# Dev.net
KiCad netlist of a schematic drawn in Altium Designer
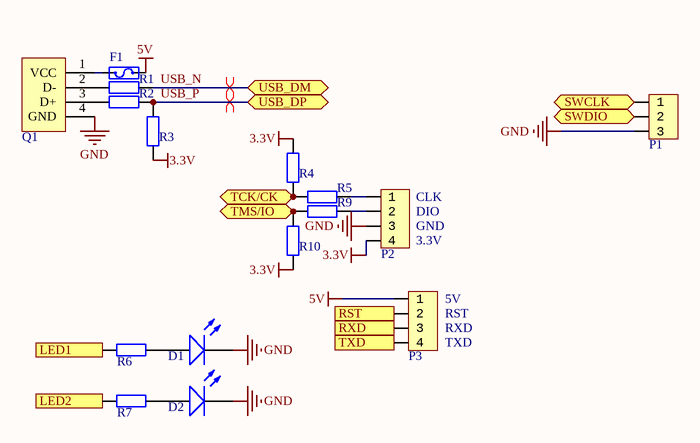
[diagram p0: Dev.SchDoc]

(export (version "E")
  (design (tool "Eeschema 10.0.6"))
  (components
    (comp (ref "D1")
      (value "RED")
      (footprint "LED-0603")
      (description "发光二极管")
      (libsource (lib "Power_Lib_Altium") (part "LED"))
    )
    (comp (ref "D2")
      (value "GREEN")
      (footprint "LED-0603")
      (description "发光二极管")
      (libsource (lib "Power_Lib_Altium") (part "LED"))
    )
    (comp (ref "F1")
      (value "Fuse")
      (footprint "R-0603")
      (description "6V 500mA 保险丝")
      (libsource (lib "Power_Lib_Altium") (part "Fuse"))
    )
    (comp (ref "P1")
      (value "HDR1x3_2.54")
      (footprint "HDR1X3_2.54_180")
      (description "Header")
      (libsource (lib "Power_Lib_Altium") (part "HDR1x3_2.54"))
    )
    (comp (ref "P2")
      (value "HDR1x4_2.54")
      (footprint "HDR1X4_2.54_180H")
      (description "Header")
      (libsource (lib "Power_Lib_Altium") (part "HDR1x4_2.54"))
    )
    (comp (ref "P3")
      (value "HDR1x4_2.54")
      (footprint "HDR1X4_2.54_180H")
      (description "Header")
      (libsource (lib "Power_Lib_Altium") (part "HDR1x4_2.54"))
    )
    (comp (ref "Q1")
      (value "USB A")
      (footprint "USB_A(M)_DIP")
      (description "USB 接口")
      (libsource (lib "Power_Lib_Altium") (part "USB A"))
    )
    (comp (ref "R1")
      (value "22R")
      (footprint "R-0603")
      (description "贴片电阻")
      (libsource (lib "Power_Lib_Altium") (part "RES"))
    )
    (comp (ref "R2")
      (value "22R")
      (footprint "R-0603")
      (description "贴片电阻")
      (libsource (lib "Power_Lib_Altium") (part "RES"))
    )
    (comp (ref "R3")
      (value "1.5K")
      (footprint "R-0603")
      (description "贴片电阻")
      (libsource (lib "") (part "RES_2"))
    )
    (comp (ref "R4")
      (value "1R")
      (footprint "R-0603")
      (description "贴片电阻")
      (libsource (lib "") (part "RES_2"))
    )
    (comp (ref "R5")
      (value "22R")
      (footprint "R-0603")
      (description "贴片电阻")
      (libsource (lib "Power_Lib_Altium") (part "RES"))
    )
    (comp (ref "R6")
      (value "10K")
      (footprint "R-0603")
      (description "贴片电阻")
      (libsource (lib "") (part "RES_1"))
    )
    (comp (ref "R7")
      (value "10K")
      (footprint "R-0603")
      (description "贴片电阻")
      (libsource (lib "") (part "RES_1"))
    )
    (comp (ref "R9")
      (value "22R")
      (footprint "R-0603")
      (description "贴片电阻")
      (libsource (lib "Power_Lib_Altium") (part "RES"))
    )
    (comp (ref "R10")
      (value "1R")
      (footprint "R-0603")
      (description "贴片电阻")
      (libsource (lib "") (part "RES_2"))
    )
  )
  (nets
    (net (code "1") (name "/LED1") (class "Default")
      (node (ref "R6") (pin "2") (pinfunction "2_2") (pintype "passive"))
    )
    (net (code "2") (name "/LED2") (class "Default")
      (node (ref "R7") (pin "2") (pinfunction "2_2") (pintype "passive"))
    )
    (net (code "3") (name "/RST") (class "Default")
      (node (ref "P3") (pin "2") (pinfunction "2_2") (pintype "passive"))
    )
    (net (code "4") (name "/RXD") (class "Default")
      (node (ref "P3") (pin "3") (pinfunction "3_3") (pintype "passive"))
    )
    (net (code "5") (name "/SWCLK") (class "Default")
      (node (ref "P1") (pin "1") (pinfunction "1_1") (pintype "passive"))
    )
    (net (code "6") (name "/SWDIO") (class "Default")
      (node (ref "P1") (pin "2") (pinfunction "2_2") (pintype "passive"))
    )
    (net (code "7") (name "/TCK{slash}CK") (class "Default")
      (node (ref "R4") (pin "1") (pinfunction "1_1") (pintype "passive"))
      (node (ref "R5") (pin "1") (pinfunction "1_1") (pintype "passive"))
    )
    (net (code "8") (name "/TMS{slash}IO") (class "Default")
      (node (ref "R10") (pin "2") (pinfunction "2_2") (pintype "passive"))
      (node (ref "R9") (pin "1") (pinfunction "1_1") (pintype "passive"))
    )
    (net (code "9") (name "/TXD") (class "Default")
      (node (ref "P3") (pin "4") (pinfunction "4_4") (pintype "passive"))
    )
    (net (code "10") (name "/USB_N") (class "Default")
      (node (ref "R1") (pin "2") (pinfunction "2_2") (pintype "passive"))
    )
    (net (code "11") (name "/USB_P") (class "Default")
      (node (ref "R2") (pin "2") (pinfunction "2_2") (pintype "passive"))
      (node (ref "R3") (pin "2") (pinfunction "2_2") (pintype "passive"))
    )
    (net (code "12") (name "3.3V") (class "Default")
      (node (ref "P2") (pin "4") (pinfunction "4_4") (pintype "passive"))
      (node (ref "R10") (pin "1") (pinfunction "1_1") (pintype "passive"))
      (node (ref "R3") (pin "1") (pinfunction "1_1") (pintype "passive"))
      (node (ref "R4") (pin "2") (pinfunction "2_2") (pintype "passive"))
    )
    (net (code "13") (name "5V") (class "Default")
      (node (ref "F1") (pin "2") (pinfunction "2_2") (pintype "passive"))
      (node (ref "P3") (pin "1") (pinfunction "1_1") (pintype "passive"))
    )
    (net (code "14") (name "GND") (class "Default")
      (node (ref "D1") (pin "K") (pinfunction "K_K") (pintype "passive"))
      (node (ref "D2") (pin "K") (pinfunction "K_K") (pintype "passive"))
      (node (ref "P1") (pin "3") (pinfunction "3_3") (pintype "passive"))
      (node (ref "P2") (pin "3") (pinfunction "3_3") (pintype "passive"))
      (node (ref "Q1") (pin "4") (pinfunction "GND_4") (pintype "passive"))
    )
    (net (code "15") (name "Net-(D1-PadA)") (class "Default")
      (node (ref "D1") (pin "A") (pinfunction "A_A") (pintype "passive"))
      (node (ref "R6") (pin "1") (pinfunction "1_1") (pintype "passive"))
    )
    (net (code "16") (name "Net-(D2-PadA)") (class "Default")
      (node (ref "D2") (pin "A") (pinfunction "A_A") (pintype "passive"))
      (node (ref "R7") (pin "1") (pinfunction "1_1") (pintype "passive"))
    )
    (net (code "17") (name "Net-(P2-Pad1)") (class "Default")
      (node (ref "P2") (pin "1") (pinfunction "1_1") (pintype "passive"))
      (node (ref "R5") (pin "2") (pinfunction "2_2") (pintype "passive"))
    )
    (net (code "18") (name "Net-(P2-Pad2)") (class "Default")
      (node (ref "P2") (pin "2") (pinfunction "2_2") (pintype "passive"))
      (node (ref "R9") (pin "2") (pinfunction "2_2") (pintype "passive"))
    )
    (net (code "19") (name "Net-(Q1-D+)") (class "Default")
      (node (ref "Q1") (pin "3") (pinfunction "D+_3") (pintype "passive"))
      (node (ref "R2") (pin "1") (pinfunction "1_1") (pintype "passive"))
    )
    (net (code "20") (name "Net-(Q1-D-)") (class "Default")
      (node (ref "Q1") (pin "2") (pinfunction "D-_2") (pintype "passive"))
      (node (ref "R1") (pin "1") (pinfunction "1_1") (pintype "passive"))
    )
    (net (code "21") (name "Net-(Q1-VCC)") (class "Default")
      (node (ref "F1") (pin "1") (pinfunction "1_1") (pintype "passive"))
      (node (ref "Q1") (pin "1") (pinfunction "VCC_1") (pintype "passive"))
    )
  )
)
